# Nu6551.net
KiCad netlist of a schematic drawn in EAGLE
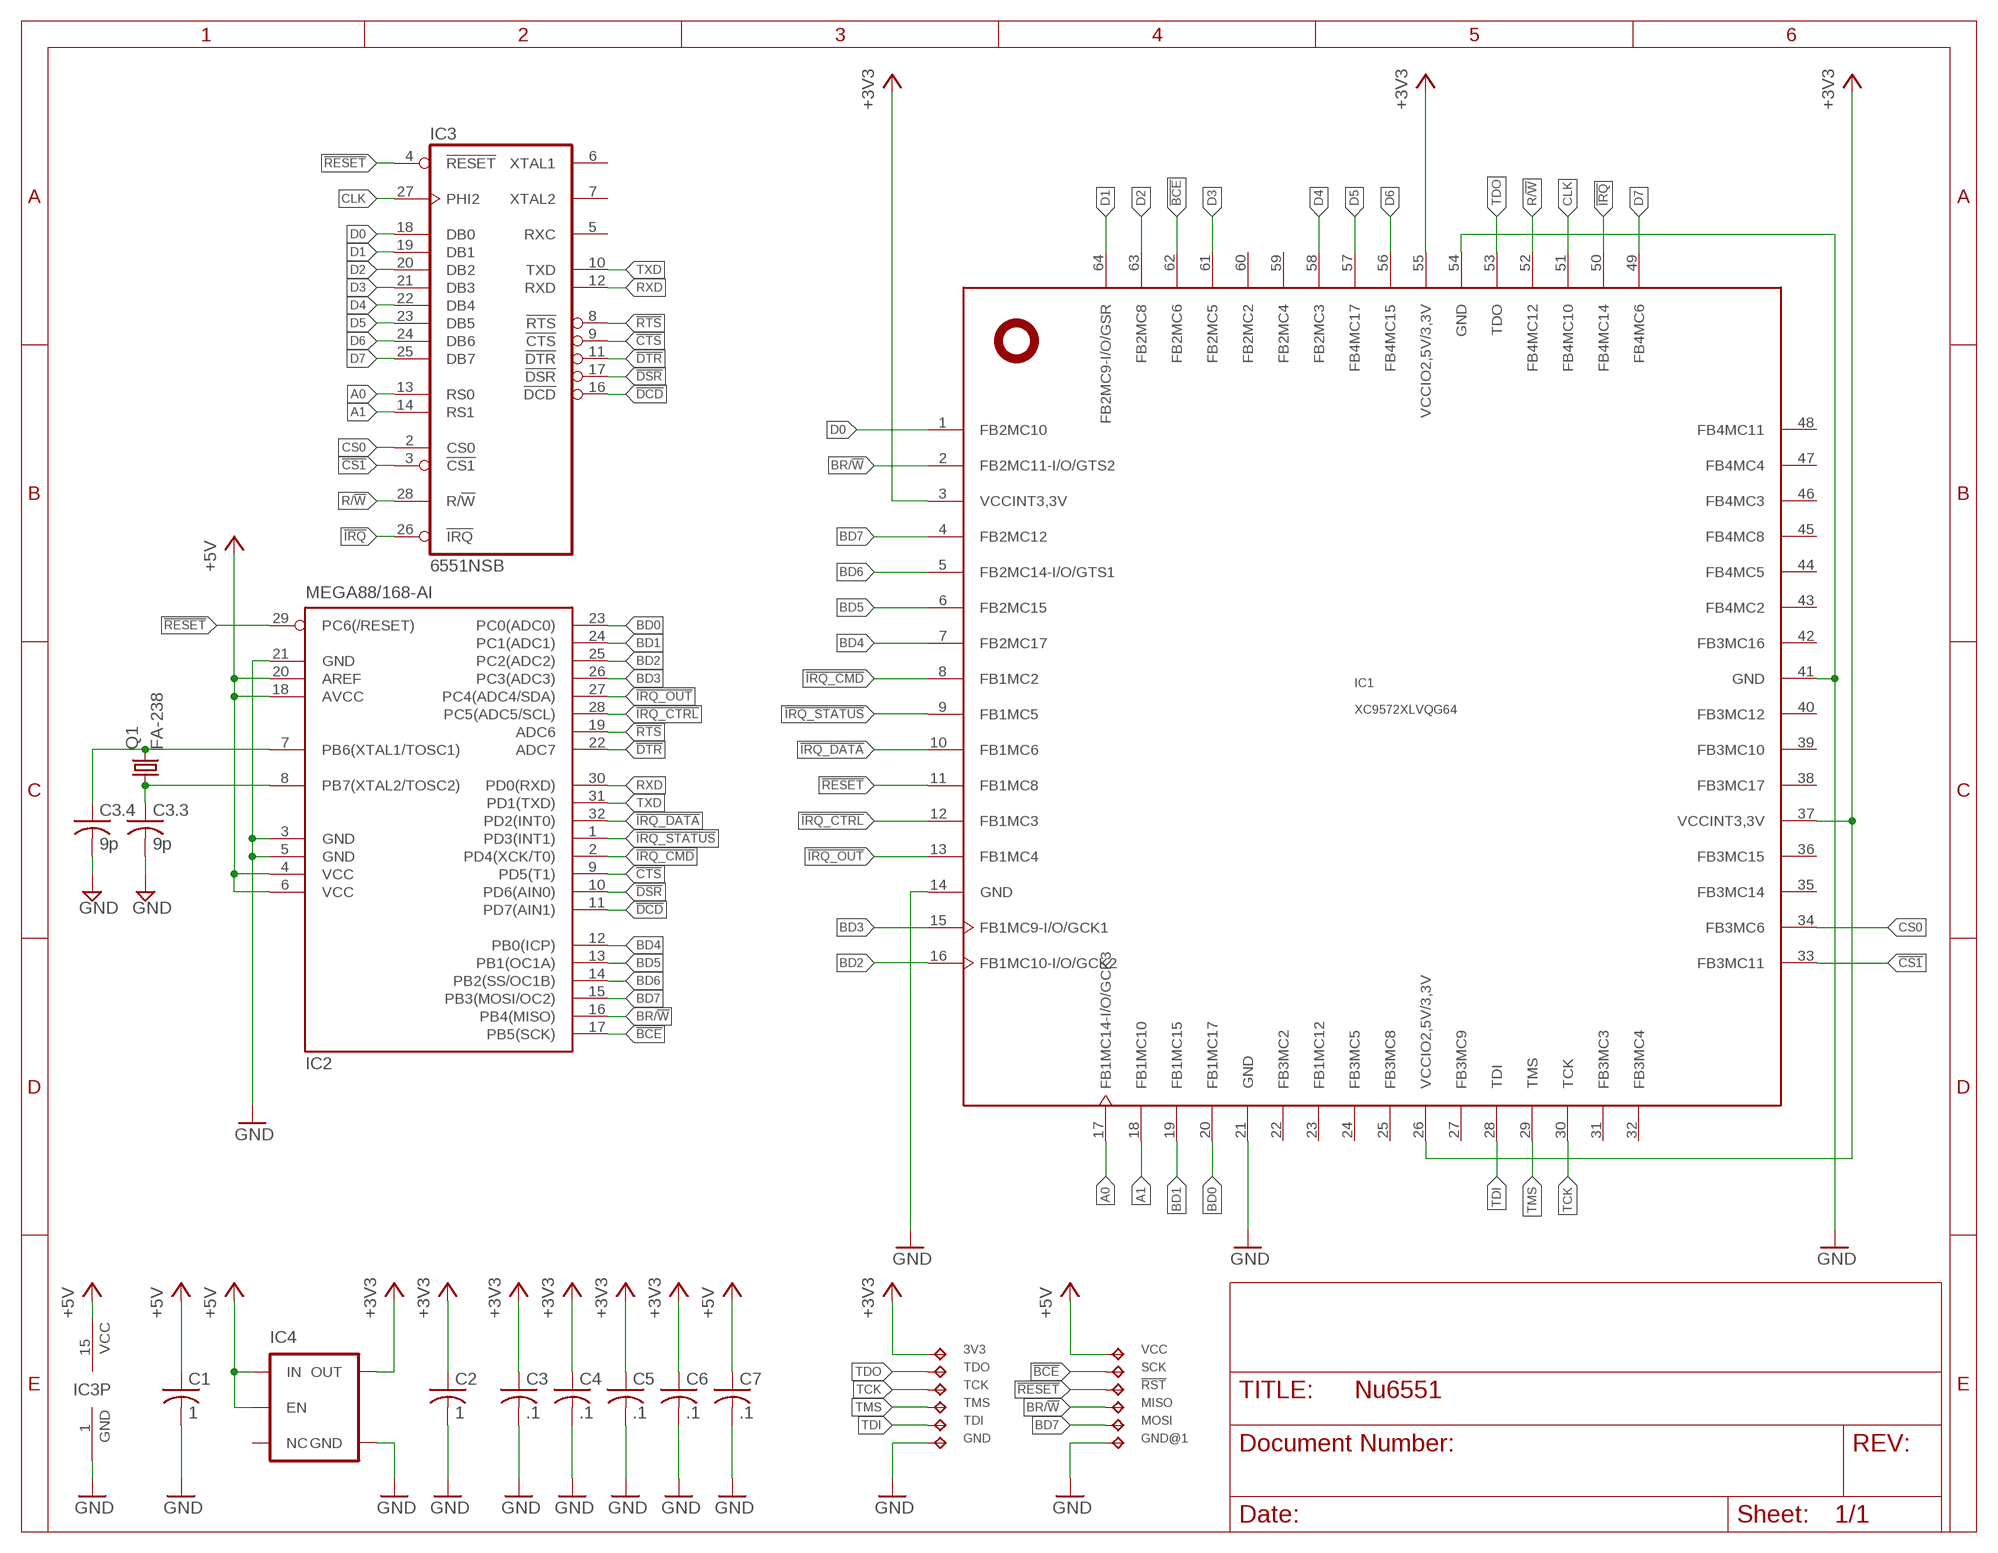
[diagram p0: schematic, sheet 1]

(export (version "E")
  (design (tool "Eeschema 10.0.6"))
  (components
    (comp (ref "!RST")
      (value "TPTP10R")
      (footprint "eagle-import:TP10R")
      (libsource (lib "eagle-import") (part "TPTP10R"))
    )
    (comp (ref "3V3")
      (value "TPTP10R")
      (footprint "eagle-import:TP10R")
      (libsource (lib "eagle-import") (part "TPTP10R"))
    )
    (comp (ref "C1")
      (value "1")
      (footprint "eagle-import:C0402")
      (libsource (lib "eagle-import") (part "resistor_C-USC0402"))
    )
    (comp (ref "C2")
      (value "1")
      (footprint "eagle-import:C0402")
      (libsource (lib "eagle-import") (part "resistor_C-USC0402"))
    )
    (comp (ref "C3")
      (value ".1")
      (footprint "eagle-import:C0402")
      (libsource (lib "eagle-import") (part "C-USC0402"))
    )
    (comp (ref "C3.3")
      (value "9p")
      (footprint "eagle-import:C0402")
      (libsource (lib "eagle-import") (part "C-USC0402"))
    )
    (comp (ref "C3.4")
      (value "9p")
      (footprint "eagle-import:C0402")
      (libsource (lib "eagle-import") (part "C-USC0402"))
    )
    (comp (ref "C4")
      (value ".1")
      (footprint "eagle-import:C0402")
      (libsource (lib "eagle-import") (part "C-USC0402"))
    )
    (comp (ref "C5")
      (value ".1")
      (footprint "eagle-import:C0402")
      (libsource (lib "eagle-import") (part "C-USC0402"))
    )
    (comp (ref "C6")
      (value ".1")
      (footprint "eagle-import:C0402")
      (libsource (lib "eagle-import") (part "C-USC0402"))
    )
    (comp (ref "C7")
      (value ".1")
      (footprint "eagle-import:C0402")
      (libsource (lib "eagle-import") (part "C-USC0402"))
    )
    (comp (ref "GND")
      (value "TPTP10R")
      (footprint "eagle-import:TP10R")
      (libsource (lib "eagle-import") (part "TPTP10R"))
    )
    (comp (ref "GND@1")
      (value "TPTP10R")
      (footprint "eagle-import:TP10R")
      (libsource (lib "eagle-import") (part "TPTP10R"))
    )
    (comp (ref "IC1")
      (value "XC9572XLVQG64")
      (footprint "eagle-import:VQFP64")
      (libsource (lib "eagle-import") (part "XC9572XLVQG64"))
    )
    (comp (ref "IC2")
      (value "MEGA88/168-AI")
      (footprint "eagle-import:TQFP32-08")
      (fields (field (name "MPN") "ATMEGA8-16AU"))
      (libsource (lib "eagle-import") (part "MEGA8-AI"))
    )
    (comp (ref "IC3")
      (value "6551NSB")
      (footprint "eagle-import:DIL28-SMD-REVERSE")
      (libsource (lib "eagle-import") (part "6551NSB"))
    )
    (comp (ref "IC4")
      (value "V_REG_TPS76433SOT23-5")
      (footprint "eagle-import:SOT23-5")
      (libsource (lib "eagle-import") (part "V_REG_TPS76433SOT23-5"))
    )
    (comp (ref "MISO")
      (value "TPTP10R")
      (footprint "eagle-import:TP10R")
      (libsource (lib "eagle-import") (part "TPTP10R"))
    )
    (comp (ref "MOSI")
      (value "TPTP10R")
      (footprint "eagle-import:TP10R")
      (libsource (lib "eagle-import") (part "TPTP10R"))
    )
    (comp (ref "Q1")
      (value "FA-238")
      (footprint "eagle-import:ASE")
      (libsource (lib "eagle-import") (part "FA-238"))
    )
    (comp (ref "SCK")
      (value "TPTP10R")
      (footprint "eagle-import:TP10R")
      (libsource (lib "eagle-import") (part "TPTP10R"))
    )
    (comp (ref "TCK")
      (value "TPTP10R")
      (footprint "eagle-import:TP10R")
      (libsource (lib "eagle-import") (part "TPTP10R"))
    )
    (comp (ref "TDI")
      (value "TPTP10R")
      (footprint "eagle-import:TP10R")
      (libsource (lib "eagle-import") (part "TPTP10R"))
    )
    (comp (ref "TDO")
      (value "TPTP10R")
      (footprint "eagle-import:TP10R")
      (libsource (lib "eagle-import") (part "TPTP10R"))
    )
    (comp (ref "TMS")
      (value "TPTP10R")
      (footprint "eagle-import:TP10R")
      (libsource (lib "eagle-import") (part "TPTP10R"))
    )
    (comp (ref "VCC")
      (value "TPTP10R")
      (footprint "eagle-import:TP10R")
      (libsource (lib "eagle-import") (part "TPTP10R"))
    )
  )
  (nets
    (net (code "1") (name "+3V3") (class "Default")
      (node (ref "3V3") (pin "TP") (pinfunction "TP_TP") (pintype "input"))
      (node (ref "C2") (pin "1") (pinfunction "1_1") (pintype "passive"))
      (node (ref "C3") (pin "1") (pinfunction "1_1") (pintype "passive"))
      (node (ref "C4") (pin "1") (pinfunction "1_1") (pintype "passive"))
      (node (ref "C5") (pin "1") (pinfunction "1_1") (pintype "passive"))
      (node (ref "C6") (pin "1") (pinfunction "1_1") (pintype "passive"))
      (node (ref "IC1") (pin "26") (pinfunction "VCCIO2,5V/3,3V_26") (pintype "power_in"))
      (node (ref "IC1") (pin "3") (pinfunction "VCCINT3,3V_3") (pintype "power_in"))
      (node (ref "IC1") (pin "37") (pinfunction "VCCINT3,3V_37") (pintype "power_in"))
      (node (ref "IC1") (pin "55") (pinfunction "VCCIO2,5V/3,3V_55") (pintype "power_in"))
      (node (ref "IC4") (pin "5") (pinfunction "OUT_5") (pintype "passive"))
    )
    (net (code "2") (name "+5V") (class "Default")
      (node (ref "C1") (pin "1") (pinfunction "1_1") (pintype "passive"))
      (node (ref "C7") (pin "1") (pinfunction "1_1") (pintype "passive"))
      (node (ref "IC2") (pin "18") (pinfunction "AVCC_18") (pintype "power_in"))
      (node (ref "IC2") (pin "20") (pinfunction "AREF_20") (pintype "passive"))
      (node (ref "IC2") (pin "4") (pinfunction "VCC_4") (pintype "power_in"))
      (node (ref "IC2") (pin "6") (pinfunction "VCC_6") (pintype "power_in"))
      (node (ref "IC3") (pin "15") (pinfunction "VCC_15") (pintype "power_in"))
      (node (ref "IC4") (pin "1") (pinfunction "IN_1") (pintype "input"))
      (node (ref "IC4") (pin "3") (pinfunction "EN_3") (pintype "input"))
      (node (ref "VCC") (pin "TP") (pinfunction "TP_TP") (pintype "input"))
    )
    (net (code "3") (name "/BR{slash}~{W}") (class "Default")
      (node (ref "IC1") (pin "2") (pinfunction "FB2MC11-I/O/GTS2_2") (pintype "bidirectional"))
      (node (ref "IC2") (pin "16") (pinfunction "PB4(MISO)_16") (pintype "bidirectional"))
      (node (ref "MISO") (pin "TP") (pinfunction "TP_TP") (pintype "input"))
    )
    (net (code "4") (name "/R{slash}~{W}") (class "Default")
      (node (ref "IC1") (pin "52") (pinfunction "FB4MC12_52") (pintype "bidirectional"))
      (node (ref "IC3") (pin "28") (pinfunction "R/~{W}_28") (pintype "input"))
    )
    (net (code "5") (name "/~{BCE}") (class "Default")
      (node (ref "IC1") (pin "62") (pinfunction "FB2MC6_62") (pintype "bidirectional"))
      (node (ref "IC2") (pin "17") (pinfunction "PB5(SCK)_17") (pintype "bidirectional"))
      (node (ref "SCK") (pin "TP") (pinfunction "TP_TP") (pintype "input"))
    )
    (net (code "6") (name "/~{CS1}") (class "Default")
      (node (ref "IC1") (pin "33") (pinfunction "FB3MC11_33") (pintype "bidirectional"))
      (node (ref "IC3") (pin "3") (pinfunction "~{CS1}_3") (pintype "input"))
    )
    (net (code "7") (name "/~{CTS}") (class "Default")
      (node (ref "IC2") (pin "9") (pinfunction "PD5(T1)_9") (pintype "bidirectional"))
      (node (ref "IC3") (pin "9") (pinfunction "~{CTS}_9") (pintype "input"))
    )
    (net (code "8") (name "/~{DCD}") (class "Default")
      (node (ref "IC2") (pin "11") (pinfunction "PD7(AIN1)_11") (pintype "bidirectional"))
      (node (ref "IC3") (pin "16") (pinfunction "~{DCD}_16") (pintype "input"))
    )
    (net (code "9") (name "/~{DSR}") (class "Default")
      (node (ref "IC2") (pin "10") (pinfunction "PD6(AIN0)_10") (pintype "bidirectional"))
      (node (ref "IC3") (pin "17") (pinfunction "~{DSR}_17") (pintype "input"))
    )
    (net (code "10") (name "/~{DTR}") (class "Default")
      (node (ref "IC2") (pin "22") (pinfunction "ADC7_22") (pintype "bidirectional"))
      (node (ref "IC3") (pin "11") (pinfunction "~{DTR}_11") (pintype "output"))
    )
    (net (code "11") (name "/~{IRQ_CMD}") (class "Default")
      (node (ref "IC1") (pin "8") (pinfunction "FB1MC2_8") (pintype "bidirectional"))
      (node (ref "IC2") (pin "2") (pinfunction "PD4(XCK/T0)_2") (pintype "bidirectional"))
    )
    (net (code "12") (name "/~{IRQ_CTRL}") (class "Default")
      (node (ref "IC1") (pin "12") (pinfunction "FB1MC3_12") (pintype "bidirectional"))
      (node (ref "IC2") (pin "28") (pinfunction "PC5(ADC5/SCL)_28") (pintype "bidirectional"))
    )
    (net (code "13") (name "/~{IRQ_DATA}") (class "Default")
      (node (ref "IC1") (pin "10") (pinfunction "FB1MC6_10") (pintype "bidirectional"))
      (node (ref "IC2") (pin "32") (pinfunction "PD2(INT0)_32") (pintype "bidirectional"))
    )
    (net (code "14") (name "/~{IRQ_OUT}") (class "Default")
      (node (ref "IC1") (pin "13") (pinfunction "FB1MC4_13") (pintype "bidirectional"))
      (node (ref "IC2") (pin "27") (pinfunction "PC4(ADC4/SDA)_27") (pintype "bidirectional"))
    )
    (net (code "15") (name "/~{IRQ_STATUS}") (class "Default")
      (node (ref "IC1") (pin "9") (pinfunction "FB1MC5_9") (pintype "bidirectional"))
      (node (ref "IC2") (pin "1") (pinfunction "PD3(INT1)_1") (pintype "bidirectional"))
    )
    (net (code "16") (name "/~{IRQ}") (class "Default")
      (node (ref "IC1") (pin "50") (pinfunction "FB4MC14_50") (pintype "bidirectional"))
      (node (ref "IC3") (pin "26") (pinfunction "~{IRQ}_26") (pintype "open_collector"))
    )
    (net (code "17") (name "/~{RESET}") (class "Default")
      (node (ref "!RST") (pin "TP") (pinfunction "TP_TP") (pintype "input"))
      (node (ref "IC1") (pin "11") (pinfunction "FB1MC8_11") (pintype "bidirectional"))
      (node (ref "IC2") (pin "29") (pinfunction "PC6(/RESET)_29") (pintype "bidirectional"))
      (node (ref "IC3") (pin "4") (pinfunction "~{RESET}_4") (pintype "input"))
    )
    (net (code "18") (name "/~{RTS}") (class "Default")
      (node (ref "IC2") (pin "19") (pinfunction "ADC6_19") (pintype "bidirectional"))
      (node (ref "IC3") (pin "8") (pinfunction "~{RTS}_8") (pintype "output"))
    )
    (net (code "19") (name "A0") (class "Default")
      (node (ref "IC1") (pin "17") (pinfunction "FB1MC14-I/O/GCK3_17") (pintype "bidirectional"))
      (node (ref "IC3") (pin "13") (pinfunction "RS0_13") (pintype "input"))
    )
    (net (code "20") (name "A1") (class "Default")
      (node (ref "IC1") (pin "18") (pinfunction "FB1MC10_18") (pintype "bidirectional"))
      (node (ref "IC3") (pin "14") (pinfunction "RS1_14") (pintype "input"))
    )
    (net (code "21") (name "BD0") (class "Default")
      (node (ref "IC1") (pin "20") (pinfunction "FB1MC17_20") (pintype "bidirectional"))
      (node (ref "IC2") (pin "23") (pinfunction "PC0(ADC0)_23") (pintype "bidirectional"))
    )
    (net (code "22") (name "BD1") (class "Default")
      (node (ref "IC1") (pin "19") (pinfunction "FB1MC15_19") (pintype "bidirectional"))
      (node (ref "IC2") (pin "24") (pinfunction "PC1(ADC1)_24") (pintype "bidirectional"))
    )
    (net (code "23") (name "BD2") (class "Default")
      (node (ref "IC1") (pin "16") (pinfunction "FB1MC10-I/O/GCK2_16") (pintype "bidirectional"))
      (node (ref "IC2") (pin "25") (pinfunction "PC2(ADC2)_25") (pintype "bidirectional"))
    )
    (net (code "24") (name "BD3") (class "Default")
      (node (ref "IC1") (pin "15") (pinfunction "FB1MC9-I/O/GCK1_15") (pintype "bidirectional"))
      (node (ref "IC2") (pin "26") (pinfunction "PC3(ADC3)_26") (pintype "bidirectional"))
    )
    (net (code "25") (name "BD4") (class "Default")
      (node (ref "IC1") (pin "7") (pinfunction "FB2MC17_7") (pintype "bidirectional"))
      (node (ref "IC2") (pin "12") (pinfunction "PB0(ICP)_12") (pintype "bidirectional"))
    )
    (net (code "26") (name "BD5") (class "Default")
      (node (ref "IC1") (pin "6") (pinfunction "FB2MC15_6") (pintype "bidirectional"))
      (node (ref "IC2") (pin "13") (pinfunction "PB1(OC1A)_13") (pintype "bidirectional"))
    )
    (net (code "27") (name "BD6") (class "Default")
      (node (ref "IC1") (pin "5") (pinfunction "FB2MC14-I/O/GTS1_5") (pintype "bidirectional"))
      (node (ref "IC2") (pin "14") (pinfunction "PB2(SS/OC1B)_14") (pintype "bidirectional"))
    )
    (net (code "28") (name "BD7") (class "Default")
      (node (ref "IC1") (pin "4") (pinfunction "FB2MC12_4") (pintype "bidirectional"))
      (node (ref "IC2") (pin "15") (pinfunction "PB3(MOSI/OC2)_15") (pintype "bidirectional"))
      (node (ref "MOSI") (pin "TP") (pinfunction "TP_TP") (pintype "input"))
    )
    (net (code "29") (name "CLK") (class "Default")
      (node (ref "IC1") (pin "51") (pinfunction "FB4MC10_51") (pintype "bidirectional"))
      (node (ref "IC3") (pin "27") (pinfunction "PHI2_27") (pintype "input"))
    )
    (net (code "30") (name "CS0") (class "Default")
      (node (ref "IC1") (pin "34") (pinfunction "FB3MC6_34") (pintype "bidirectional"))
      (node (ref "IC3") (pin "2") (pinfunction "CS0_2") (pintype "input"))
    )
    (net (code "31") (name "D0") (class "Default")
      (node (ref "IC1") (pin "1") (pinfunction "FB2MC10_1") (pintype "bidirectional"))
      (node (ref "IC3") (pin "18") (pinfunction "DB0_18") (pintype "bidirectional"))
    )
    (net (code "32") (name "D1") (class "Default")
      (node (ref "IC1") (pin "64") (pinfunction "FB2MC9-I/O/GSR_64") (pintype "bidirectional"))
      (node (ref "IC3") (pin "19") (pinfunction "DB1_19") (pintype "bidirectional"))
    )
    (net (code "33") (name "D2") (class "Default")
      (node (ref "IC1") (pin "63") (pinfunction "FB2MC8_63") (pintype "bidirectional"))
      (node (ref "IC3") (pin "20") (pinfunction "DB2_20") (pintype "bidirectional"))
    )
    (net (code "34") (name "D3") (class "Default")
      (node (ref "IC1") (pin "61") (pinfunction "FB2MC5_61") (pintype "bidirectional"))
      (node (ref "IC3") (pin "21") (pinfunction "DB3_21") (pintype "bidirectional"))
    )
    (net (code "35") (name "D4") (class "Default")
      (node (ref "IC1") (pin "58") (pinfunction "FB2MC3_58") (pintype "bidirectional"))
      (node (ref "IC3") (pin "22") (pinfunction "DB4_22") (pintype "bidirectional"))
    )
    (net (code "36") (name "D5") (class "Default")
      (node (ref "IC1") (pin "57") (pinfunction "FB4MC17_57") (pintype "bidirectional"))
      (node (ref "IC3") (pin "23") (pinfunction "DB5_23") (pintype "bidirectional"))
    )
    (net (code "37") (name "D6") (class "Default")
      (node (ref "IC1") (pin "56") (pinfunction "FB4MC15_56") (pintype "bidirectional"))
      (node (ref "IC3") (pin "24") (pinfunction "DB6_24") (pintype "bidirectional"))
    )
    (net (code "38") (name "D7") (class "Default")
      (node (ref "IC1") (pin "49") (pinfunction "FB4MC6_49") (pintype "bidirectional"))
      (node (ref "IC3") (pin "25") (pinfunction "DB7_25") (pintype "bidirectional"))
    )
    (net (code "39") (name "GND") (class "Default")
      (node (ref "C1") (pin "2") (pinfunction "2_2") (pintype "passive"))
      (node (ref "C2") (pin "2") (pinfunction "2_2") (pintype "passive"))
      (node (ref "C3") (pin "2") (pinfunction "2_2") (pintype "passive"))
      (node (ref "C3.3") (pin "2") (pinfunction "2_2") (pintype "passive"))
      (node (ref "C3.4") (pin "2") (pinfunction "2_2") (pintype "passive"))
      (node (ref "C4") (pin "2") (pinfunction "2_2") (pintype "passive"))
      (node (ref "C5") (pin "2") (pinfunction "2_2") (pintype "passive"))
      (node (ref "C6") (pin "2") (pinfunction "2_2") (pintype "passive"))
      (node (ref "C7") (pin "2") (pinfunction "2_2") (pintype "passive"))
      (node (ref "GND") (pin "TP") (pinfunction "TP_TP") (pintype "input"))
      (node (ref "GND@1") (pin "TP") (pinfunction "TP_TP") (pintype "input"))
      (node (ref "IC1") (pin "14") (pinfunction "GND_14") (pintype "power_in"))
      (node (ref "IC1") (pin "21") (pinfunction "GND_21") (pintype "power_in"))
      (node (ref "IC1") (pin "41") (pinfunction "GND_41") (pintype "power_in"))
      (node (ref "IC1") (pin "54") (pinfunction "GND_54") (pintype "power_in"))
      (node (ref "IC2") (pin "21") (pinfunction "GND_21") (pintype "power_in"))
      (node (ref "IC2") (pin "3") (pinfunction "GND_3") (pintype "power_in"))
      (node (ref "IC2") (pin "5") (pinfunction "GND_5") (pintype "power_in"))
      (node (ref "IC3") (pin "1") (pinfunction "GND_1") (pintype "power_in"))
      (node (ref "IC4") (pin "2") (pinfunction "GND_2") (pintype "input"))
    )
    (net (code "40") (name "Net-(IC2-PB6(XTAL1{slash}TOSC1))") (class "Default")
      (node (ref "C3.4") (pin "1") (pinfunction "1_1") (pintype "passive"))
      (node (ref "IC2") (pin "7") (pinfunction "PB6(XTAL1/TOSC1)_7") (pintype "bidirectional"))
      (node (ref "Q1") (pin "3") (pinfunction "2_3") (pintype "passive"))
    )
    (net (code "41") (name "Net-(IC2-PB7(XTAL2{slash}TOSC2))") (class "Default")
      (node (ref "C3.3") (pin "1") (pinfunction "1_1") (pintype "passive"))
      (node (ref "IC2") (pin "8") (pinfunction "PB7(XTAL2/TOSC2)_8") (pintype "bidirectional"))
      (node (ref "Q1") (pin "1") (pinfunction "1_1") (pintype "passive"))
    )
    (net (code "42") (name "RXD") (class "Default")
      (node (ref "IC2") (pin "30") (pinfunction "PD0(RXD)_30") (pintype "bidirectional"))
      (node (ref "IC3") (pin "12") (pinfunction "RXD_12") (pintype "input"))
    )
    (net (code "43") (name "TCK") (class "Default")
      (node (ref "IC1") (pin "30") (pinfunction "TCK_30") (pintype "bidirectional"))
      (node (ref "TCK") (pin "TP") (pinfunction "TP_TP") (pintype "input"))
    )
    (net (code "44") (name "TDI") (class "Default")
      (node (ref "IC1") (pin "28") (pinfunction "TDI_28") (pintype "bidirectional"))
      (node (ref "TDI") (pin "TP") (pinfunction "TP_TP") (pintype "input"))
    )
    (net (code "45") (name "TDO") (class "Default")
      (node (ref "IC1") (pin "53") (pinfunction "TDO_53") (pintype "bidirectional"))
      (node (ref "TDO") (pin "TP") (pinfunction "TP_TP") (pintype "input"))
    )
    (net (code "46") (name "TMS") (class "Default")
      (node (ref "IC1") (pin "29") (pinfunction "TMS_29") (pintype "bidirectional"))
      (node (ref "TMS") (pin "TP") (pinfunction "TP_TP") (pintype "input"))
    )
    (net (code "47") (name "TXD") (class "Default")
      (node (ref "IC2") (pin "31") (pinfunction "PD1(TXD)_31") (pintype "bidirectional"))
      (node (ref "IC3") (pin "10") (pinfunction "TXD_10") (pintype "output"))
    )
    (net (code "48") (name "unconnected-(IC1-FB1MC12-Pad23)") (class "Default")
      (node (ref "IC1") (pin "23") (pinfunction "FB1MC12_23") (pintype "bidirectional"))
    )
    (net (code "49") (name "unconnected-(IC1-FB2MC2-Pad60)") (class "Default")
      (node (ref "IC1") (pin "60") (pinfunction "FB2MC2_60") (pintype "bidirectional"))
    )
    (net (code "50") (name "unconnected-(IC1-FB2MC4-Pad59)") (class "Default")
      (node (ref "IC1") (pin "59") (pinfunction "FB2MC4_59") (pintype "bidirectional"))
    )
    (net (code "51") (name "unconnected-(IC1-FB3MC2-Pad22)") (class "Default")
      (node (ref "IC1") (pin "22") (pinfunction "FB3MC2_22") (pintype "bidirectional"))
    )
    (net (code "52") (name "unconnected-(IC1-FB3MC3-Pad31)") (class "Default")
      (node (ref "IC1") (pin "31") (pinfunction "FB3MC3_31") (pintype "bidirectional"))
    )
    (net (code "53") (name "unconnected-(IC1-FB3MC4-Pad32)") (class "Default")
      (node (ref "IC1") (pin "32") (pinfunction "FB3MC4_32") (pintype "bidirectional"))
    )
    (net (code "54") (name "unconnected-(IC1-FB3MC5-Pad24)") (class "Default")
      (node (ref "IC1") (pin "24") (pinfunction "FB3MC5_24") (pintype "bidirectional"))
    )
    (net (code "55") (name "unconnected-(IC1-FB3MC8-Pad25)") (class "Default")
      (node (ref "IC1") (pin "25") (pinfunction "FB3MC8_25") (pintype "bidirectional"))
    )
    (net (code "56") (name "unconnected-(IC1-FB3MC9-Pad27)") (class "Default")
      (node (ref "IC1") (pin "27") (pinfunction "FB3MC9_27") (pintype "bidirectional"))
    )
    (net (code "57") (name "unconnected-(IC1-FB3MC10-Pad39)") (class "Default")
      (node (ref "IC1") (pin "39") (pinfunction "FB3MC10_39") (pintype "bidirectional"))
    )
    (net (code "58") (name "unconnected-(IC1-FB3MC12-Pad40)") (class "Default")
      (node (ref "IC1") (pin "40") (pinfunction "FB3MC12_40") (pintype "bidirectional"))
    )
    (net (code "59") (name "unconnected-(IC1-FB3MC14-Pad35)") (class "Default")
      (node (ref "IC1") (pin "35") (pinfunction "FB3MC14_35") (pintype "bidirectional"))
    )
    (net (code "60") (name "unconnected-(IC1-FB3MC15-Pad36)") (class "Default")
      (node (ref "IC1") (pin "36") (pinfunction "FB3MC15_36") (pintype "bidirectional"))
    )
    (net (code "61") (name "unconnected-(IC1-FB3MC16-Pad42)") (class "Default")
      (node (ref "IC1") (pin "42") (pinfunction "FB3MC16_42") (pintype "bidirectional"))
    )
    (net (code "62") (name "unconnected-(IC1-FB3MC17-Pad38)") (class "Default")
      (node (ref "IC1") (pin "38") (pinfunction "FB3MC17_38") (pintype "bidirectional"))
    )
    (net (code "63") (name "unconnected-(IC1-FB4MC2-Pad43)") (class "Default")
      (node (ref "IC1") (pin "43") (pinfunction "FB4MC2_43") (pintype "bidirectional"))
    )
    (net (code "64") (name "unconnected-(IC1-FB4MC3-Pad46)") (class "Default")
      (node (ref "IC1") (pin "46") (pinfunction "FB4MC3_46") (pintype "bidirectional"))
    )
    (net (code "65") (name "unconnected-(IC1-FB4MC4-Pad47)") (class "Default")
      (node (ref "IC1") (pin "47") (pinfunction "FB4MC4_47") (pintype "bidirectional"))
    )
    (net (code "66") (name "unconnected-(IC1-FB4MC5-Pad44)") (class "Default")
      (node (ref "IC1") (pin "44") (pinfunction "FB4MC5_44") (pintype "bidirectional"))
    )
    (net (code "67") (name "unconnected-(IC1-FB4MC8-Pad45)") (class "Default")
      (node (ref "IC1") (pin "45") (pinfunction "FB4MC8_45") (pintype "bidirectional"))
    )
    (net (code "68") (name "unconnected-(IC1-FB4MC11-Pad48)") (class "Default")
      (node (ref "IC1") (pin "48") (pinfunction "FB4MC11_48") (pintype "bidirectional"))
    )
    (net (code "69") (name "unconnected-(IC3A-RXC-Pad5)") (class "Default")
      (node (ref "IC3") (pin "5") (pinfunction "RXC_5") (pintype "bidirectional"))
    )
    (net (code "70") (name "unconnected-(IC3A-XTAL1-Pad6)") (class "Default")
      (node (ref "IC3") (pin "6") (pinfunction "XTAL1_6") (pintype "bidirectional"))
    )
    (net (code "71") (name "unconnected-(IC3A-XTAL2-Pad7)") (class "Default")
      (node (ref "IC3") (pin "7") (pinfunction "XTAL2_7") (pintype "bidirectional"))
    )
    (net (code "72") (name "unconnected-(IC4-NC-Pad4)") (class "Default")
      (node (ref "IC4") (pin "4") (pinfunction "NC_4") (pintype "input"))
    )
  )
)
